# RF.net
KiCad netlist of a schematic drawn in Altium Designer
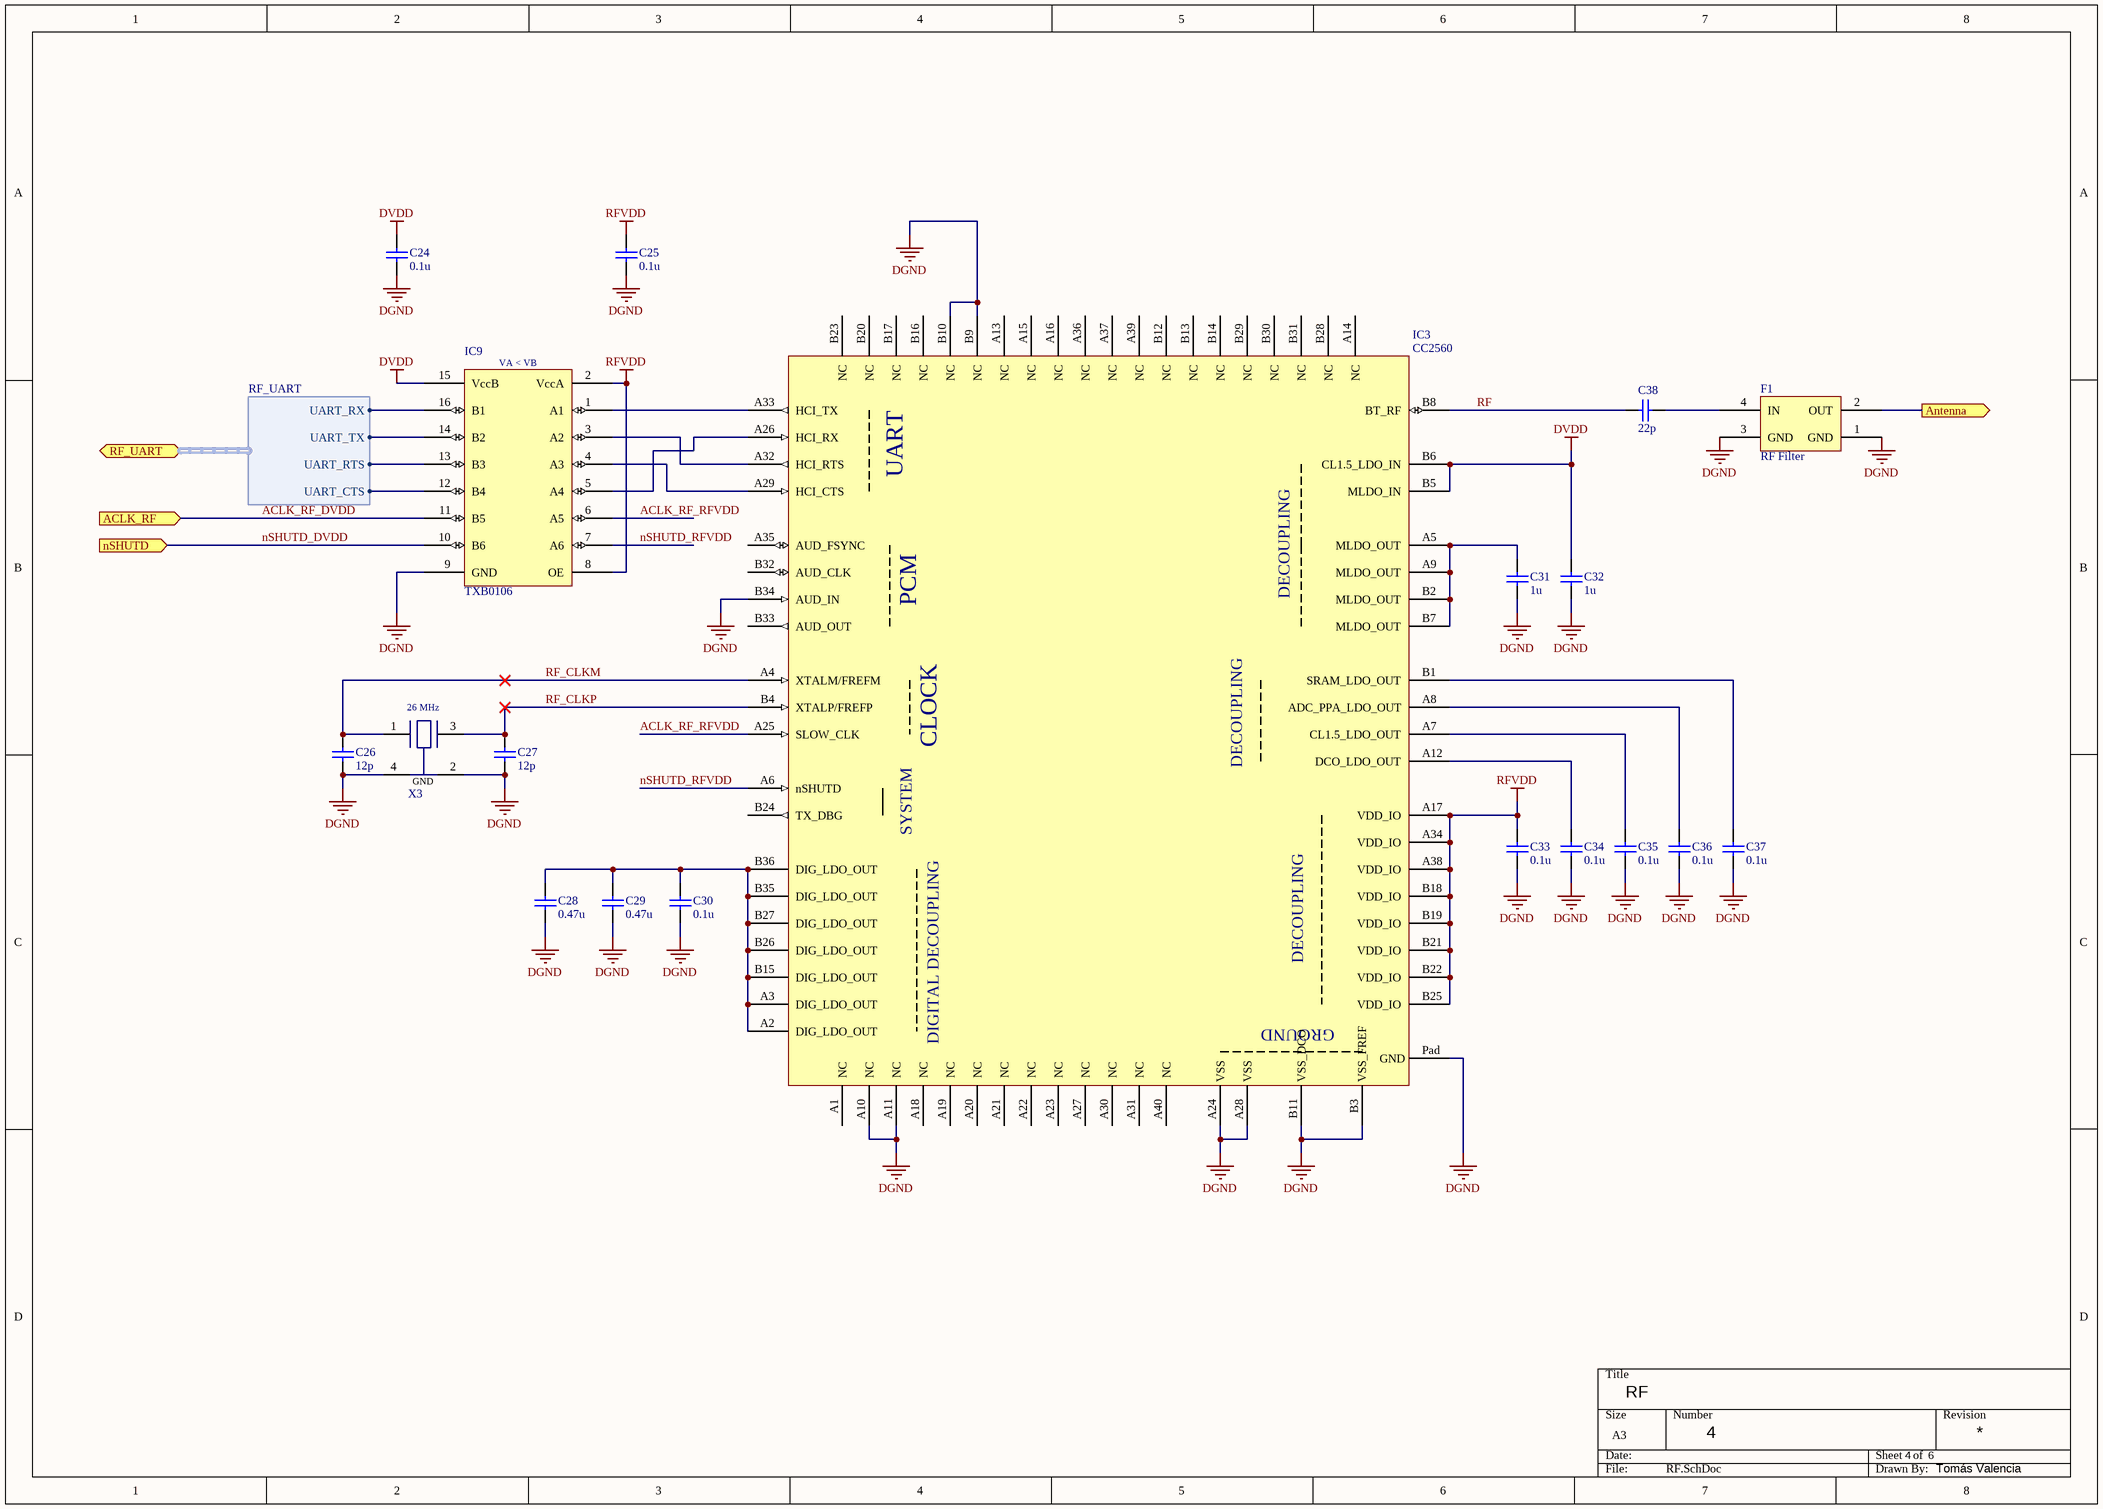
[diagram p0: RF.SchDoc]

(export (version "E")
  (design (tool "Eeschema 10.0.6"))
  (components
    (comp (ref "C24")
      (value "0.1u")
      (footprint "C0603")
      (description "Capacitor")
      (libsource (lib "Common Devices") (part "Capacitor"))
    )
    (comp (ref "C25")
      (value "0.1u")
      (footprint "C0603")
      (description "Capacitor")
      (libsource (lib "Common Devices") (part "Capacitor"))
    )
    (comp (ref "C26")
      (value "12p")
      (footprint "C0603")
      (description "Capacitor")
      (libsource (lib "Common Devices") (part "Capacitor"))
    )
    (comp (ref "C27")
      (value "12p")
      (footprint "C0603")
      (description "Capacitor")
      (libsource (lib "Common Devices") (part "Capacitor"))
    )
    (comp (ref "C28")
      (value "0.47u")
      (footprint "C0603")
      (description "Capacitor")
      (libsource (lib "Common Devices") (part "Capacitor"))
    )
    (comp (ref "C29")
      (value "0.47u")
      (footprint "C0603")
      (description "Capacitor")
      (libsource (lib "Common Devices") (part "Capacitor"))
    )
    (comp (ref "C30")
      (value "0.1u")
      (footprint "C0603")
      (description "Capacitor")
      (libsource (lib "Common Devices") (part "Capacitor"))
    )
    (comp (ref "C31")
      (value "1u")
      (footprint "C0603")
      (description "Capacitor")
      (libsource (lib "Common Devices") (part "Capacitor"))
    )
    (comp (ref "C32")
      (value "1u")
      (footprint "C0603")
      (description "Capacitor")
      (libsource (lib "Common Devices") (part "Capacitor"))
    )
    (comp (ref "C33")
      (value "0.1u")
      (footprint "C0603")
      (description "Capacitor")
      (libsource (lib "Common Devices") (part "Capacitor"))
    )
    (comp (ref "C34")
      (value "0.1u")
      (footprint "C0603")
      (description "Capacitor")
      (libsource (lib "Common Devices") (part "Capacitor"))
    )
    (comp (ref "C35")
      (value "0.1u")
      (footprint "C0603")
      (description "Capacitor")
      (libsource (lib "Common Devices") (part "Capacitor"))
    )
    (comp (ref "C36")
      (value "0.1u")
      (footprint "C0603")
      (description "Capacitor")
      (libsource (lib "Common Devices") (part "Capacitor"))
    )
    (comp (ref "C37")
      (value "0.1u")
      (footprint "C0603")
      (description "Capacitor")
      (libsource (lib "Common Devices") (part "Capacitor"))
    )
    (comp (ref "C38")
      (value "22p")
      (footprint "C0603")
      (description "Capacitor")
      (libsource (lib "Common Devices") (part "Capacitor"))
    )
    (comp (ref "F1")
      (value "RF Filter")
      (footprint "LFB212G45SG8A127")
      (description "RF Filter 2.4 GHz")
      (libsource (lib "Main Board") (part "LFB212G45SG8A127"))
    )
    (comp (ref "IC3") (value "CC2560") (footprint "CC2560") (libsource (lib "Main Board") (part "CC2560")))
    (comp (ref "IC9") (value "TXB0106") (footprint "TXB0106") (libsource (lib "Main Board") (part "TXB0106")))
    (comp (ref "X3")
      (value "XTAL_26_MHz")
      (footprint "XTAL_26MHZ")
      (libsource (lib "Main Board") (part "XTAL_26_MHz"))
    )
  )
  (nets
    (net (code "2") (name "/ACLK_RF_DVDD") (class "Default")
      (node (ref "IC9") (pin "11") (pinfunction "B5_11") (pintype "bidirectional"))
    )
    (net (code "3") (name "/ACLK_RF_RFVDD") (class "Default")
      (node (ref "IC3") (pin "A25") (pinfunction "SLOW_CLK_A25") (pintype "input"))
      (node (ref "IC9") (pin "6") (pinfunction "A5_6") (pintype "bidirectional"))
    )
    (net (code "4") (name "/Antenna") (class "Default")
      (node (ref "F1") (pin "2") (pinfunction "OUT_2") (pintype "passive"))
    )
    (net (code "5") (name "/RF") (class "Default")
      (node (ref "C38") (pin "1") (pinfunction "1_1") (pintype "passive"))
      (node (ref "IC3") (pin "B8") (pinfunction "BT_RF_B8") (pintype "bidirectional"))
    )
    (net (code "6") (name "/RF_CLKM") (class "Default")
      (node (ref "C26") (pin "2") (pinfunction "2_2") (pintype "passive"))
      (node (ref "IC3") (pin "A4") (pinfunction "XTALM/FREFM_A4") (pintype "input"))
      (node (ref "X3") (pin "1") (pinfunction "OUT_1") (pintype "passive"))
    )
    (net (code "7") (name "/RF_CLKP") (class "Default")
      (node (ref "C27") (pin "2") (pinfunction "2_2") (pintype "passive"))
      (node (ref "IC3") (pin "B4") (pinfunction "XTALP/FREFP_B4") (pintype "input"))
      (node (ref "X3") (pin "3") (pinfunction "IN_3") (pintype "passive"))
    )
    (net (code "8") (name "/UART_CTS") (class "Default")
      (node (ref "IC9") (pin "12") (pinfunction "B4_12") (pintype "bidirectional"))
    )
    (net (code "9") (name "/UART_RTS") (class "Default")
      (node (ref "IC9") (pin "13") (pinfunction "B3_13") (pintype "bidirectional"))
    )
    (net (code "10") (name "/UART_RX") (class "Default")
      (node (ref "IC9") (pin "16") (pinfunction "B1_16") (pintype "bidirectional"))
    )
    (net (code "11") (name "/UART_TX") (class "Default")
      (node (ref "IC9") (pin "14") (pinfunction "B2_14") (pintype "bidirectional"))
    )
    (net (code "12") (name "/nSHUTD_DVDD") (class "Default")
      (node (ref "IC9") (pin "10") (pinfunction "B6_10") (pintype "bidirectional"))
    )
    (net (code "13") (name "/nSHUTD_RFVDD") (class "Default")
      (node (ref "IC3") (pin "A6") (pinfunction "nSHUTD_A6") (pintype "input"))
      (node (ref "IC9") (pin "7") (pinfunction "A6_7") (pintype "bidirectional"))
    )
    (net (code "15") (name "DGND") (class "Default")
      (node (ref "C24") (pin "1") (pinfunction "1_1") (pintype "passive"))
      (node (ref "C25") (pin "1") (pinfunction "1_1") (pintype "passive"))
      (node (ref "C26") (pin "1") (pinfunction "1_1") (pintype "passive"))
      (node (ref "C27") (pin "1") (pinfunction "1_1") (pintype "passive"))
      (node (ref "C28") (pin "1") (pinfunction "1_1") (pintype "passive"))
      (node (ref "C29") (pin "1") (pinfunction "1_1") (pintype "passive"))
      (node (ref "C30") (pin "1") (pinfunction "1_1") (pintype "passive"))
      (node (ref "C31") (pin "1") (pinfunction "1_1") (pintype "passive"))
      (node (ref "C32") (pin "1") (pinfunction "1_1") (pintype "passive"))
      (node (ref "C33") (pin "1") (pinfunction "1_1") (pintype "passive"))
      (node (ref "C34") (pin "1") (pinfunction "1_1") (pintype "passive"))
      (node (ref "C35") (pin "1") (pinfunction "1_1") (pintype "passive"))
      (node (ref "C36") (pin "1") (pinfunction "1_1") (pintype "passive"))
      (node (ref "C37") (pin "1") (pinfunction "1_1") (pintype "passive"))
      (node (ref "F1") (pin "1") (pinfunction "GND_1") (pintype "power_in"))
      (node (ref "F1") (pin "3") (pinfunction "GND_3") (pintype "power_in"))
      (node (ref "IC3") (pin "A10") (pinfunction "NC_A10") (pintype "passive"))
      (node (ref "IC3") (pin "A11") (pinfunction "NC_A11") (pintype "passive"))
      (node (ref "IC3") (pin "A24") (pinfunction "VSS_A24") (pintype "power_in"))
      (node (ref "IC3") (pin "A28") (pinfunction "VSS_A28") (pintype "power_in"))
      (node (ref "IC3") (pin "B10") (pinfunction "NC_B10") (pintype "passive"))
      (node (ref "IC3") (pin "B11") (pinfunction "VSS_DCO_B11") (pintype "power_in"))
      (node (ref "IC3") (pin "B3") (pinfunction "VSS_FREF_B3") (pintype "power_in"))
      (node (ref "IC3") (pin "B34") (pinfunction "AUD_IN_B34") (pintype "input"))
      (node (ref "IC3") (pin "B9") (pinfunction "NC_B9") (pintype "passive"))
      (node (ref "IC3") (pin "Pad") (pinfunction "GND_Pad") (pintype "power_in"))
      (node (ref "IC9") (pin "9") (pinfunction "GND_9") (pintype "power_in"))
      (node (ref "X3") (pin "2") (pinfunction "GND_2") (pintype "passive"))
      (node (ref "X3") (pin "4") (pinfunction "GND_4") (pintype "passive"))
    )
    (net (code "16") (name "DVDD") (class "Default")
      (node (ref "C24") (pin "2") (pinfunction "2_2") (pintype "passive"))
      (node (ref "C32") (pin "2") (pinfunction "2_2") (pintype "passive"))
      (node (ref "IC3") (pin "B5") (pinfunction "MLDO_IN_B5") (pintype "power_in"))
      (node (ref "IC3") (pin "B6") (pinfunction "CL1.5_LDO_IN_B6") (pintype "power_in"))
      (node (ref "IC9") (pin "15") (pinfunction "VccB_15") (pintype "passive"))
    )
    (net (code "17") (name "Net-(C28-Pad2)") (class "Default")
      (node (ref "C28") (pin "2") (pinfunction "2_2") (pintype "passive"))
      (node (ref "C29") (pin "2") (pinfunction "2_2") (pintype "passive"))
      (node (ref "C30") (pin "2") (pinfunction "2_2") (pintype "passive"))
      (node (ref "IC3") (pin "A2") (pinfunction "DIG_LDO_OUT_A2") (pintype "power_in"))
      (node (ref "IC3") (pin "A3") (pinfunction "DIG_LDO_OUT_A3") (pintype "power_in"))
      (node (ref "IC3") (pin "B15") (pinfunction "DIG_LDO_OUT_B15") (pintype "power_in"))
      (node (ref "IC3") (pin "B26") (pinfunction "DIG_LDO_OUT_B26") (pintype "power_in"))
      (node (ref "IC3") (pin "B27") (pinfunction "DIG_LDO_OUT_B27") (pintype "power_in"))
      (node (ref "IC3") (pin "B35") (pinfunction "DIG_LDO_OUT_B35") (pintype "power_in"))
      (node (ref "IC3") (pin "B36") (pinfunction "DIG_LDO_OUT_B36") (pintype "power_in"))
    )
    (net (code "18") (name "Net-(C31-Pad2)") (class "Default")
      (node (ref "C31") (pin "2") (pinfunction "2_2") (pintype "passive"))
      (node (ref "IC3") (pin "A5") (pinfunction "MLDO_OUT_A5") (pintype "power_in"))
      (node (ref "IC3") (pin "A9") (pinfunction "MLDO_OUT_A9") (pintype "power_in"))
      (node (ref "IC3") (pin "B2") (pinfunction "MLDO_OUT_B2") (pintype "power_in"))
      (node (ref "IC3") (pin "B7") (pinfunction "MLDO_OUT_B7") (pintype "power_in"))
    )
    (net (code "19") (name "Net-(F1-IN)") (class "Default")
      (node (ref "C38") (pin "2") (pinfunction "2_2") (pintype "passive"))
      (node (ref "F1") (pin "4") (pinfunction "IN_4") (pintype "power_in"))
    )
    (net (code "20") (name "Net-(IC3-ADC_PPA_LDO_OUT)") (class "Default")
      (node (ref "C36") (pin "2") (pinfunction "2_2") (pintype "passive"))
      (node (ref "IC3") (pin "A8") (pinfunction "ADC_PPA_LDO_OUT_A8") (pintype "power_in"))
    )
    (net (code "21") (name "Net-(IC3-CL1.5_LDO_OUT)") (class "Default")
      (node (ref "C35") (pin "2") (pinfunction "2_2") (pintype "passive"))
      (node (ref "IC3") (pin "A7") (pinfunction "CL1.5_LDO_OUT_A7") (pintype "power_in"))
    )
    (net (code "22") (name "Net-(IC3-DCO_LDO_OUT)") (class "Default")
      (node (ref "C34") (pin "2") (pinfunction "2_2") (pintype "passive"))
      (node (ref "IC3") (pin "A12") (pinfunction "DCO_LDO_OUT_A12") (pintype "power_in"))
    )
    (net (code "23") (name "Net-(IC3-HCI_CTS)") (class "Default")
      (node (ref "IC3") (pin "A29") (pinfunction "HCI_CTS_A29") (pintype "input"))
      (node (ref "IC9") (pin "4") (pinfunction "A3_4") (pintype "bidirectional"))
    )
    (net (code "24") (name "Net-(IC3-HCI_RTS)") (class "Default")
      (node (ref "IC3") (pin "A32") (pinfunction "HCI_RTS_A32") (pintype "output"))
      (node (ref "IC9") (pin "3") (pinfunction "A2_3") (pintype "bidirectional"))
    )
    (net (code "25") (name "Net-(IC3-HCI_RX)") (class "Default")
      (node (ref "IC3") (pin "A26") (pinfunction "HCI_RX_A26") (pintype "input"))
      (node (ref "IC9") (pin "5") (pinfunction "A4_5") (pintype "bidirectional"))
    )
    (net (code "26") (name "Net-(IC3-HCI_TX)") (class "Default")
      (node (ref "IC3") (pin "A33") (pinfunction "HCI_TX_A33") (pintype "output"))
      (node (ref "IC9") (pin "1") (pinfunction "A1_1") (pintype "bidirectional"))
    )
    (net (code "27") (name "Net-(IC3-SRAM_LDO_OUT)") (class "Default")
      (node (ref "C37") (pin "2") (pinfunction "2_2") (pintype "passive"))
      (node (ref "IC3") (pin "B1") (pinfunction "SRAM_LDO_OUT_B1") (pintype "power_in"))
    )
    (net (code "28") (name "RFVDD") (class "Default")
      (node (ref "C25") (pin "2") (pinfunction "2_2") (pintype "passive"))
      (node (ref "C33") (pin "2") (pinfunction "2_2") (pintype "passive"))
      (node (ref "IC3") (pin "A17") (pinfunction "VDD_IO_A17") (pintype "power_in"))
      (node (ref "IC3") (pin "A34") (pinfunction "VDD_IO_A34") (pintype "power_in"))
      (node (ref "IC3") (pin "A38") (pinfunction "VDD_IO_A38") (pintype "power_in"))
      (node (ref "IC3") (pin "B18") (pinfunction "VDD_IO_B18") (pintype "power_in"))
      (node (ref "IC3") (pin "B19") (pinfunction "VDD_IO_B19") (pintype "power_in"))
      (node (ref "IC3") (pin "B21") (pinfunction "VDD_IO_B21") (pintype "power_in"))
      (node (ref "IC3") (pin "B22") (pinfunction "VDD_IO_B22") (pintype "power_in"))
      (node (ref "IC3") (pin "B25") (pinfunction "VDD_IO_B25") (pintype "power_in"))
      (node (ref "IC9") (pin "2") (pinfunction "VccA_2") (pintype "power_in"))
      (node (ref "IC9") (pin "8") (pinfunction "OE_8") (pintype "passive"))
    )
    (net (code "29") (name "unconnected-(IC3-AUD_CLK-PadB32)") (class "Default")
      (node (ref "IC3") (pin "B32") (pinfunction "AUD_CLK_B32") (pintype "bidirectional"))
    )
    (net (code "30") (name "unconnected-(IC3-AUD_FSYNC-PadA35)") (class "Default")
      (node (ref "IC3") (pin "A35") (pinfunction "AUD_FSYNC_A35") (pintype "bidirectional"))
    )
    (net (code "31") (name "unconnected-(IC3-AUD_OUT-PadB33)") (class "Default")
      (node (ref "IC3") (pin "B33") (pinfunction "AUD_OUT_B33") (pintype "output"))
    )
    (net (code "32") (name "unconnected-(IC3-NC-PadA1)") (class "Default")
      (node (ref "IC3") (pin "A1") (pinfunction "NC_A1") (pintype "passive"))
    )
    (net (code "33") (name "unconnected-(IC3-NC-PadA13)") (class "Default")
      (node (ref "IC3") (pin "A13") (pinfunction "NC_A13") (pintype "passive"))
    )
    (net (code "34") (name "unconnected-(IC3-NC-PadA14)") (class "Default")
      (node (ref "IC3") (pin "A14") (pinfunction "NC_A14") (pintype "passive"))
    )
    (net (code "35") (name "unconnected-(IC3-NC-PadA15)") (class "Default")
      (node (ref "IC3") (pin "A15") (pinfunction "NC_A15") (pintype "passive"))
    )
    (net (code "36") (name "unconnected-(IC3-NC-PadA16)") (class "Default")
      (node (ref "IC3") (pin "A16") (pinfunction "NC_A16") (pintype "passive"))
    )
    (net (code "37") (name "unconnected-(IC3-NC-PadA18)") (class "Default")
      (node (ref "IC3") (pin "A18") (pinfunction "NC_A18") (pintype "passive"))
    )
    (net (code "38") (name "unconnected-(IC3-NC-PadA19)") (class "Default")
      (node (ref "IC3") (pin "A19") (pinfunction "NC_A19") (pintype "passive"))
    )
    (net (code "39") (name "unconnected-(IC3-NC-PadA20)") (class "Default")
      (node (ref "IC3") (pin "A20") (pinfunction "NC_A20") (pintype "passive"))
    )
    (net (code "40") (name "unconnected-(IC3-NC-PadA21)") (class "Default")
      (node (ref "IC3") (pin "A21") (pinfunction "NC_A21") (pintype "passive"))
    )
    (net (code "41") (name "unconnected-(IC3-NC-PadA22)") (class "Default")
      (node (ref "IC3") (pin "A22") (pinfunction "NC_A22") (pintype "passive"))
    )
    (net (code "42") (name "unconnected-(IC3-NC-PadA23)") (class "Default")
      (node (ref "IC3") (pin "A23") (pinfunction "NC_A23") (pintype "passive"))
    )
    (net (code "43") (name "unconnected-(IC3-NC-PadA27)") (class "Default")
      (node (ref "IC3") (pin "A27") (pinfunction "NC_A27") (pintype "passive"))
    )
    (net (code "44") (name "unconnected-(IC3-NC-PadA30)") (class "Default")
      (node (ref "IC3") (pin "A30") (pinfunction "NC_A30") (pintype "passive"))
    )
    (net (code "45") (name "unconnected-(IC3-NC-PadA31)") (class "Default")
      (node (ref "IC3") (pin "A31") (pinfunction "NC_A31") (pintype "passive"))
    )
    (net (code "46") (name "unconnected-(IC3-NC-PadA36)") (class "Default")
      (node (ref "IC3") (pin "A36") (pinfunction "NC_A36") (pintype "passive"))
    )
    (net (code "47") (name "unconnected-(IC3-NC-PadA37)") (class "Default")
      (node (ref "IC3") (pin "A37") (pinfunction "NC_A37") (pintype "passive"))
    )
    (net (code "48") (name "unconnected-(IC3-NC-PadA39)") (class "Default")
      (node (ref "IC3") (pin "A39") (pinfunction "NC_A39") (pintype "passive"))
    )
    (net (code "49") (name "unconnected-(IC3-NC-PadA40)") (class "Default")
      (node (ref "IC3") (pin "A40") (pinfunction "NC_A40") (pintype "passive"))
    )
    (net (code "50") (name "unconnected-(IC3-NC-PadB12)") (class "Default")
      (node (ref "IC3") (pin "B12") (pinfunction "NC_B12") (pintype "passive"))
    )
    (net (code "51") (name "unconnected-(IC3-NC-PadB13)") (class "Default")
      (node (ref "IC3") (pin "B13") (pinfunction "NC_B13") (pintype "passive"))
    )
    (net (code "52") (name "unconnected-(IC3-NC-PadB14)") (class "Default")
      (node (ref "IC3") (pin "B14") (pinfunction "NC_B14") (pintype "passive"))
    )
    (net (code "53") (name "unconnected-(IC3-NC-PadB16)") (class "Default")
      (node (ref "IC3") (pin "B16") (pinfunction "NC_B16") (pintype "passive"))
    )
    (net (code "54") (name "unconnected-(IC3-NC-PadB17)") (class "Default")
      (node (ref "IC3") (pin "B17") (pinfunction "NC_B17") (pintype "passive"))
    )
    (net (code "55") (name "unconnected-(IC3-NC-PadB20)") (class "Default")
      (node (ref "IC3") (pin "B20") (pinfunction "NC_B20") (pintype "passive"))
    )
    (net (code "56") (name "unconnected-(IC3-NC-PadB23)") (class "Default")
      (node (ref "IC3") (pin "B23") (pinfunction "NC_B23") (pintype "passive"))
    )
    (net (code "57") (name "unconnected-(IC3-NC-PadB28)") (class "Default")
      (node (ref "IC3") (pin "B28") (pinfunction "NC_B28") (pintype "passive"))
    )
    (net (code "58") (name "unconnected-(IC3-NC-PadB29)") (class "Default")
      (node (ref "IC3") (pin "B29") (pinfunction "NC_B29") (pintype "passive"))
    )
    (net (code "59") (name "unconnected-(IC3-NC-PadB30)") (class "Default")
      (node (ref "IC3") (pin "B30") (pinfunction "NC_B30") (pintype "passive"))
    )
    (net (code "60") (name "unconnected-(IC3-NC-PadB31)") (class "Default")
      (node (ref "IC3") (pin "B31") (pinfunction "NC_B31") (pintype "passive"))
    )
    (net (code "61") (name "unconnected-(IC3-TX_DBG-PadB24)") (class "Default")
      (node (ref "IC3") (pin "B24") (pinfunction "TX_DBG_B24") (pintype "output"))
    )
  )
)
